# Sheet_Business_Card.net
KiCad netlist of a schematic drawn in Altium Designer
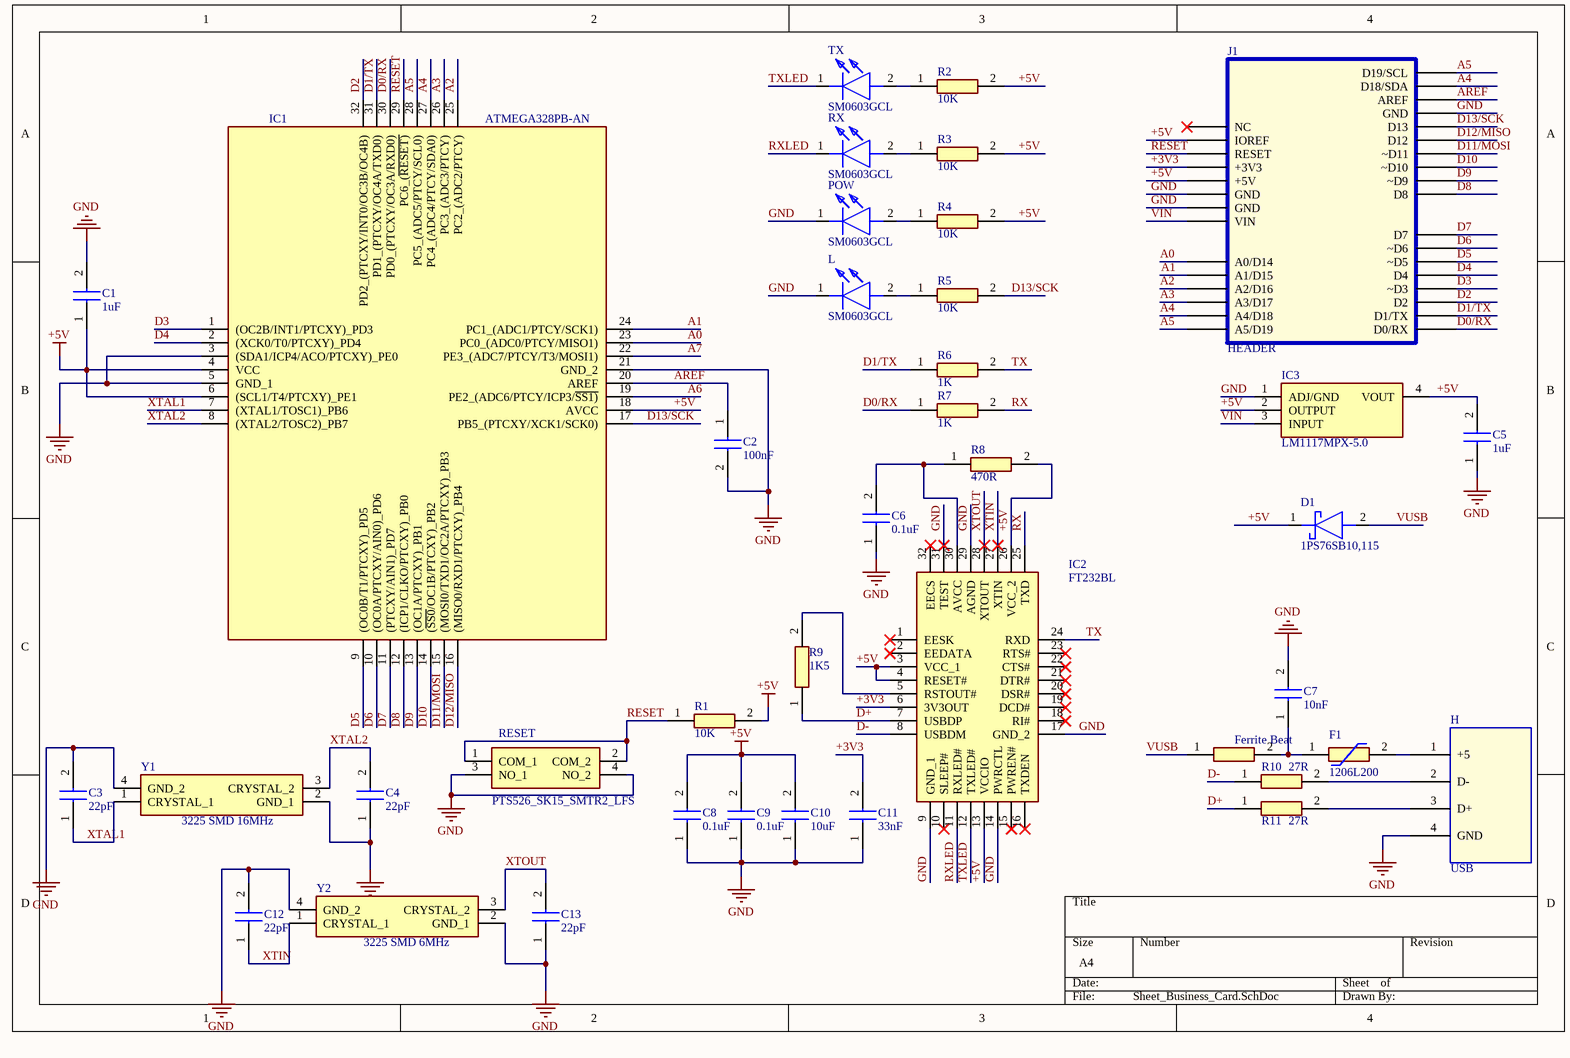
[diagram p0: Sheet_Business_Card.SchDoc]

(export (version "E")
  (design (tool "Eeschema 10.0.6"))
  (components
    (comp (ref "C1")
      (value "1uF")
      (footprint "SamacSys:CAPC1608X90N")
      (description "Capacitor")
      (fields
        (field (name "MANUFACTURER_PART_NUMBER") "06035C105KAT2A")
        (field (name "MOUSER PART NUMBER") "581-06035C105KAT2A")
      )
      (libsource (lib "*") (part "06035C105KAT2A"))
    )
    (comp (ref "C2")
      (value "100nF")
      (footprint "SamacSys:CAPC1608X90N")
      (description "Capacitor")
      (fields
        (field (name "MANUFACTURER_PART_NUMBER") "06035C105KAT2A")
        (field (name "MOUSER PART NUMBER") "581-06035C105KAT2A")
      )
      (libsource (lib "*") (part "06035C105KAT2A"))
    )
    (comp (ref "C3")
      (value "22pF")
      (footprint "SamacSys:CAPC1608X90N")
      (description "Capacitor")
      (fields
        (field (name "MANUFACTURER_PART_NUMBER") "06035C105KAT2A")
        (field (name "MOUSER PART NUMBER") "581-06035C105KAT2A")
      )
      (libsource (lib "*") (part "06035C105KAT2A"))
    )
    (comp (ref "C4")
      (value "22pF")
      (footprint "SamacSys:CAPC1608X90N")
      (description "Capacitor")
      (fields
        (field (name "MANUFACTURER_PART_NUMBER") "06035C105KAT2A")
        (field (name "MOUSER PART NUMBER") "581-06035C105KAT2A")
      )
      (libsource (lib "*") (part "06035C105KAT2A"))
    )
    (comp (ref "C5")
      (value "1uF")
      (footprint "SamacSys:CAPC1608X90N")
      (description "Capacitor")
      (fields
        (field (name "MANUFACTURER_PART_NUMBER") "06035C105KAT2A")
        (field (name "MOUSER PART NUMBER") "581-06035C105KAT2A")
      )
      (libsource (lib "*") (part "06035C105KAT2A"))
    )
    (comp (ref "C6")
      (value "0.1uF")
      (footprint "SamacSys:CAPC1608X90N")
      (description "Capacitor")
      (fields
        (field (name "MANUFACTURER_PART_NUMBER") "06035C105KAT2A")
        (field (name "MOUSER PART NUMBER") "581-06035C105KAT2A")
      )
      (libsource (lib "*") (part "06035C105KAT2A"))
    )
    (comp (ref "C7")
      (value "10nF")
      (footprint "SamacSys:CAPC1608X90N")
      (description "Capacitor")
      (fields
        (field (name "MANUFACTURER_PART_NUMBER") "06035C105KAT2A")
        (field (name "MOUSER PART NUMBER") "581-06035C105KAT2A")
      )
      (libsource (lib "*") (part "06035C105KAT2A"))
    )
    (comp (ref "C8")
      (value "0.1uF")
      (footprint "SamacSys:CAPC1608X90N")
      (description "Capacitor")
      (fields
        (field (name "MANUFACTURER_PART_NUMBER") "06035C105KAT2A")
        (field (name "MOUSER PART NUMBER") "581-06035C105KAT2A")
      )
      (libsource (lib "*") (part "06035C105KAT2A"))
    )
    (comp (ref "C9")
      (value "0.1uF")
      (footprint "SamacSys:CAPC1608X90N")
      (description "Capacitor")
      (fields
        (field (name "MANUFACTURER_PART_NUMBER") "06035C105KAT2A")
        (field (name "MOUSER PART NUMBER") "581-06035C105KAT2A")
      )
      (libsource (lib "*") (part "06035C105KAT2A"))
    )
    (comp (ref "C10")
      (value "10uF")
      (footprint "SamacSys:CAPC1608X90N")
      (description "Capacitor")
      (fields
        (field (name "MANUFACTURER_PART_NUMBER") "06035C105KAT2A")
        (field (name "MOUSER PART NUMBER") "581-06035C105KAT2A")
      )
      (libsource (lib "*") (part "06035C105KAT2A"))
    )
    (comp (ref "C11")
      (value "33nF")
      (footprint "SamacSys:CAPC1608X90N")
      (description "Capacitor")
      (fields
        (field (name "MANUFACTURER_PART_NUMBER") "06035C105KAT2A")
        (field (name "MOUSER PART NUMBER") "581-06035C105KAT2A")
      )
      (libsource (lib "*") (part "06035C105KAT2A"))
    )
    (comp (ref "C12")
      (value "22pF")
      (footprint "SamacSys:CAPC1608X90N")
      (description "Capacitor")
      (fields
        (field (name "MANUFACTURER_PART_NUMBER") "06035C105KAT2A")
        (field (name "MOUSER PART NUMBER") "581-06035C105KAT2A")
      )
      (libsource (lib "*") (part "06035C105KAT2A"))
    )
    (comp (ref "C13")
      (value "22pF")
      (footprint "SamacSys:CAPC1608X90N")
      (description "Capacitor")
      (fields
        (field (name "MANUFACTURER_PART_NUMBER") "06035C105KAT2A")
        (field (name "MOUSER PART NUMBER") "581-06035C105KAT2A")
      )
      (libsource (lib "*") (part "06035C105KAT2A"))
    )
    (comp (ref "D1")
      (value "1PS76SB10,115")
      (footprint "SamacSys:SOD2512X110N")
      (description "Schottky Diode")
      (fields (field (name "MOUSER PART NUMBER") "771-1PS76SB10-T/R"))
      (libsource (lib "SamacSys") (part "1PS76SB10,115"))
    )
    (comp (ref "F1")
      (value "1206L200")
      (footprint "SamacSys:1206L05015YR")
      (description "Resettable Fuse")
      (libsource (lib "SamacSys") (part "1206L200"))
    )
    (comp (ref "FB")
      (value "Ferrite Beat")
      (footprint "SamacSys:RESC1608X55N")
      (description "Resistor")
      (fields
        (field (name "MANUFACTURER_PART_NUMBER") "KTR03EZPF1501")
        (field (name "MOUSER PART NUMBER") "755-KTR03EZPF1501")
      )
      (libsource (lib "SamacSys") (part "KTR03EZPF1501"))
    )
    (comp (ref "H") (value "USB") (footprint "USB_FLAT") (libsource (lib "BisnessCard") (part "USB")))
    (comp (ref "IC1")
      (value "ATMEGA328PB-AN")
      (footprint "SamacSys:QFP80P900X900X120-32N")
      (description "Integrated Circuit")
      (fields (field (name "MOUSER PART NUMBER") "556-ATMEGA328PB-AN"))
      (libsource (lib "*") (part "ATMEGA328PB-AN"))
    )
    (comp (ref "IC2")
      (value "FT232BL")
      (footprint "SamacSys:QFP80P900X900X160-32N")
      (description "Integrated Circuit")
      (libsource (lib "*") (part "FT232BL"))
    )
    (comp (ref "IC3")
      (value "LM1117MPX-5.0")
      (footprint "SamacSys:SOT230P700X180-4N")
      (description "Integrated Circuit")
      (fields (field (name "MOUSER PART NUMBER") "926-LM1117MPX-50"))
      (libsource (lib "SamacSys") (part "LM1117MPX-5.0"))
    )
    (comp (ref "J1")
      (value "HEADER")
      (footprint "Conector Arduino UNO")
      (libsource (lib "BisnessCard") (part "HEDER ARDUINO UNO"))
    )
    (comp (ref "L")
      (value "SM0603GCL")
      (footprint "SamacSys:LEDC1608X60N")
      (description "LED")
      (fields (field (name "MOUSER PART NUMBER") "749-SM0603GCL"))
      (libsource (lib "SamacSys") (part "SM0603GCL"))
    )
    (comp (ref "POW")
      (value "SM0603GCL")
      (footprint "SamacSys:LEDC1608X60N")
      (description "LED")
      (fields (field (name "MOUSER PART NUMBER") "749-SM0603GCL"))
      (libsource (lib "SamacSys") (part "SM0603GCL"))
    )
    (comp (ref "R1")
      (value "10K")
      (footprint "SamacSys:RESC1608X55N")
      (description "Resistor")
      (fields
        (field (name "MANUFACTURER_PART_NUMBER") "KTR03EZPF1501")
        (field (name "MOUSER PART NUMBER") "755-KTR03EZPF1501")
      )
      (libsource (lib "SamacSys") (part "KTR03EZPF1501"))
    )
    (comp (ref "R2")
      (value "10K")
      (footprint "SamacSys:RESC1608X55N")
      (description "Resistor")
      (fields
        (field (name "MANUFACTURER_PART_NUMBER") "KTR03EZPF1501")
        (field (name "MOUSER PART NUMBER") "755-KTR03EZPF1501")
      )
      (libsource (lib "SamacSys") (part "KTR03EZPF1501"))
    )
    (comp (ref "R3")
      (value "10K")
      (footprint "SamacSys:RESC1608X55N")
      (description "Resistor")
      (fields
        (field (name "MANUFACTURER_PART_NUMBER") "KTR03EZPF1501")
        (field (name "MOUSER PART NUMBER") "755-KTR03EZPF1501")
      )
      (libsource (lib "SamacSys") (part "KTR03EZPF1501"))
    )
    (comp (ref "R4")
      (value "10K")
      (footprint "SamacSys:RESC1608X55N")
      (description "Resistor")
      (fields
        (field (name "MANUFACTURER_PART_NUMBER") "KTR03EZPF1501")
        (field (name "MOUSER PART NUMBER") "755-KTR03EZPF1501")
      )
      (libsource (lib "SamacSys") (part "KTR03EZPF1501"))
    )
    (comp (ref "R5")
      (value "10K")
      (footprint "SamacSys:RESC1608X55N")
      (description "Resistor")
      (fields
        (field (name "MANUFACTURER_PART_NUMBER") "KTR03EZPF1501")
        (field (name "MOUSER PART NUMBER") "755-KTR03EZPF1501")
      )
      (libsource (lib "SamacSys") (part "KTR03EZPF1501"))
    )
    (comp (ref "R6")
      (value "1K")
      (footprint "SamacSys:RESC1608X55N")
      (description "Resistor")
      (fields
        (field (name "MANUFACTURER_PART_NUMBER") "KTR03EZPF1501")
        (field (name "MOUSER PART NUMBER") "755-KTR03EZPF1501")
      )
      (libsource (lib "SamacSys") (part "KTR03EZPF1501"))
    )
    (comp (ref "R7")
      (value "1K")
      (footprint "SamacSys:RESC1608X55N")
      (description "Resistor")
      (fields
        (field (name "MANUFACTURER_PART_NUMBER") "KTR03EZPF1501")
        (field (name "MOUSER PART NUMBER") "755-KTR03EZPF1501")
      )
      (libsource (lib "SamacSys") (part "KTR03EZPF1501"))
    )
    (comp (ref "R8")
      (value "470R")
      (footprint "SamacSys:RESC1608X55N")
      (description "Resistor")
      (fields
        (field (name "MANUFACTURER_PART_NUMBER") "KTR03EZPF1501")
        (field (name "MOUSER PART NUMBER") "755-KTR03EZPF1501")
      )
      (libsource (lib "SamacSys") (part "KTR03EZPF1501"))
    )
    (comp (ref "R9")
      (value "1K5")
      (footprint "SamacSys:RESC1608X55N")
      (description "Resistor")
      (fields
        (field (name "MANUFACTURER_PART_NUMBER") "KTR03EZPF1501")
        (field (name "MOUSER PART NUMBER") "755-KTR03EZPF1501")
      )
      (libsource (lib "") (part "KTR03EZPF1501_1"))
    )
    (comp (ref "R10")
      (value "27R")
      (footprint "SamacSys:RESC1608X55N")
      (description "Resistor")
      (fields
        (field (name "MANUFACTURER_PART_NUMBER") "KTR03EZPF1501")
        (field (name "MOUSER PART NUMBER") "755-KTR03EZPF1501")
      )
      (libsource (lib "SamacSys") (part "KTR03EZPF1501"))
    )
    (comp (ref "R11")
      (value "27R")
      (footprint "SamacSys:RESC1608X55N")
      (description "Resistor")
      (fields
        (field (name "MANUFACTURER_PART_NUMBER") "KTR03EZPF1501")
        (field (name "MOUSER PART NUMBER") "755-KTR03EZPF1501")
      )
      (libsource (lib "SamacSys") (part "KTR03EZPF1501"))
    )
    (comp (ref "RESET")
      (value "PTS526_SK15_SMTR2_LFS")
      (footprint "SamacSys:PTS526SK15SMTR2LFS")
      (description "Switch")
      (fields
        (field (name "MANUFACTURER_PART_NUMBER") "PTS526 SK15 SMTR2 LFS")
        (field (name "MOUSER PART NUMBER") "611-PTS526SK15SMR2L")
      )
      (libsource (lib "*") (part "PTS526_SK15_SMTR2_LFS"))
    )
    (comp (ref "RX")
      (value "SM0603GCL")
      (footprint "SamacSys:LEDC1608X60N")
      (description "LED")
      (fields (field (name "MOUSER PART NUMBER") "749-SM0603GCL"))
      (libsource (lib "SamacSys") (part "SM0603GCL"))
    )
    (comp (ref "TX")
      (value "SM0603GCL")
      (footprint "SamacSys:LEDC1608X60N")
      (description "LED")
      (fields (field (name "MOUSER PART NUMBER") "749-SM0603GCL"))
      (libsource (lib "SamacSys") (part "SM0603GCL"))
    )
    (comp (ref "Y1")
      (value "TSX-3225_16.0000MF18X-AC0")
      (footprint "SamacSys:TSX3225160000MF18XAC0")
      (description "Crystal or Oscillator 16MHz")
      (fields
        (field (name "MANUFACTURER_PART_NUMBER") "TSX-3225 16.0000MF18X-AC0")
        (field (name "MOUSER PART NUMBER") "732-322516F18XAC0")
      )
      (libsource (lib "*") (part "TSX-3225_16.0000MF18X-AC0"))
    )
    (comp (ref "Y2")
      (value "TSX-3225_16.0000MF18X-AC0")
      (footprint "SamacSys:TSX3225160000MF18XAC0")
      (description "Crystal or Oscillator 6 MHz")
      (fields
        (field (name "MANUFACTURER_PART_NUMBER") "TSX-3225 16.0000MF18X-AC0")
        (field (name "MOUSER PART NUMBER") "732-322516F18XAC0")
      )
      (libsource (lib "*") (part "TSX-3225_16.0000MF18X-AC0"))
    )
  )
  (nets
    (net (code "1") (name "+5V") (class "Default")
      (node (ref "C1") (pin "1") (pinfunction "1_1") (pintype "passive"))
      (node (ref "C10") (pin "2") (pinfunction "2_2") (pintype "passive"))
      (node (ref "C5") (pin "2") (pinfunction "2_2") (pintype "passive"))
      (node (ref "C8") (pin "2") (pinfunction "2_2") (pintype "passive"))
      (node (ref "C9") (pin "2") (pinfunction "2_2") (pintype "passive"))
      (node (ref "D1") (pin "1") (pinfunction "K_1") (pintype "passive"))
      (node (ref "IC1") (pin "18") (pinfunction "AVCC_18") (pintype "passive"))
      (node (ref "IC1") (pin "4") (pinfunction "VCC_4") (pintype "passive"))
      (node (ref "IC1") (pin "6") (pinfunction "(SCL1/T4/PTCXY)_PE1_6") (pintype "passive"))
      (node (ref "IC2") (pin "13") (pinfunction "VCCIO_13") (pintype "passive"))
      (node (ref "IC2") (pin "26") (pinfunction "VCC_2_26") (pintype "passive"))
      (node (ref "IC2") (pin "3") (pinfunction "VCC_1_3") (pintype "passive"))
      (node (ref "IC2") (pin "4") (pinfunction "RESET#_4") (pintype "passive"))
      (node (ref "IC3") (pin "2") (pinfunction "OUTPUT_2") (pintype "passive"))
      (node (ref "IC3") (pin "4") (pinfunction "VOUT_4") (pintype "passive"))
      (node (ref "J1") (pin "4") (pinfunction "IOREF_4") (pintype "passive"))
      (node (ref "R1") (pin "2") (pinfunction "2_2") (pintype "passive"))
      (node (ref "R2") (pin "2") (pinfunction "2_2") (pintype "passive"))
      (node (ref "R3") (pin "2") (pinfunction "2_2") (pintype "passive"))
      (node (ref "R4") (pin "2") (pinfunction "2_2") (pintype "passive"))
      (node (ref "R8") (pin "2") (pinfunction "2_2") (pintype "passive"))
    )
    (net (code "2") (name "/+3V3") (class "Default")
      (node (ref "C11") (pin "2") (pinfunction "2_2") (pintype "passive"))
      (node (ref "IC2") (pin "6") (pinfunction "3V3OUT_6") (pintype "passive"))
      (node (ref "J1") (pin "6") (pinfunction "+3V3_6") (pintype "passive"))
    )
    (net (code "3") (name "/A0") (class "Default")
      (node (ref "IC1") (pin "23") (pinfunction "PC0_(ADC0/PTCY/MISO1)_23") (pintype "passive"))
      (node (ref "J1") (pin "23") (pinfunction "A0/D14_23") (pintype "passive"))
    )
    (net (code "4") (name "/A1") (class "Default")
      (node (ref "IC1") (pin "24") (pinfunction "PC1_(ADC1/PTCY/SCK1)_24") (pintype "passive"))
      (node (ref "J1") (pin "24") (pinfunction "A1/D15_24") (pintype "passive"))
    )
    (net (code "5") (name "/A2") (class "Default")
      (node (ref "IC1") (pin "25") (pinfunction "PC2_(ADC2/PTCY)_25") (pintype "passive"))
      (node (ref "J1") (pin "25") (pinfunction "A2/D16_25") (pintype "passive"))
    )
    (net (code "6") (name "/A3") (class "Default")
      (node (ref "IC1") (pin "26") (pinfunction "PC3_(ADC3/PTCY)_26") (pintype "passive"))
      (node (ref "J1") (pin "26") (pinfunction "A3/D17_26") (pintype "passive"))
    )
    (net (code "7") (name "/A4") (class "Default")
      (node (ref "IC1") (pin "27") (pinfunction "PC4_(ADC4/PTCY/SDA0)_27") (pintype "passive"))
      (node (ref "J1") (pin "27") (pinfunction "A4/D18_27") (pintype "passive"))
    )
    (net (code "8") (name "/A5") (class "Default")
      (node (ref "IC1") (pin "28") (pinfunction "PC5_(ADC5/PTCY/SCL0)_28") (pintype "passive"))
      (node (ref "J1") (pin "28") (pinfunction "A5/D19_28") (pintype "passive"))
    )
    (net (code "9") (name "/A6") (class "Default")
      (node (ref "IC1") (pin "19") (pinfunction "PE2_(ADC6/PTCY/ICP3/~{SS1)}_19") (pintype "passive"))
    )
    (net (code "10") (name "/A7") (class "Default")
      (node (ref "IC1") (pin "22") (pinfunction "PE3_(ADC7/PTCY/T3/MOSI1)_22") (pintype "passive"))
    )
    (net (code "11") (name "/AREF") (class "Default")
      (node (ref "C2") (pin "1") (pinfunction "1_1") (pintype "passive"))
      (node (ref "IC1") (pin "20") (pinfunction "AREF_20") (pintype "passive"))
      (node (ref "J1") (pin "20") (pinfunction "AREF_20") (pintype "passive"))
    )
    (net (code "12") (name "/D+") (class "Default")
      (node (ref "IC2") (pin "7") (pinfunction "USBDP_7") (pintype "passive"))
      (node (ref "R11") (pin "1") (pinfunction "1_1") (pintype "passive"))
      (node (ref "R9") (pin "1") (pinfunction "1_1") (pintype "passive"))
    )
    (net (code "13") (name "/D-") (class "Default")
      (node (ref "IC2") (pin "8") (pinfunction "USBDM_8") (pintype "passive"))
      (node (ref "R10") (pin "1") (pinfunction "1_1") (pintype "passive"))
    )
    (net (code "14") (name "/D0{slash}RX") (class "Default")
      (node (ref "IC1") (pin "30") (pinfunction "PD0_(PTCXY/OC3A/RXD0)_30") (pintype "passive"))
      (node (ref "J1") (pin "30") (pinfunction "D0/RX_30") (pintype "passive"))
      (node (ref "R7") (pin "1") (pinfunction "1_1") (pintype "passive"))
    )
    (net (code "15") (name "/D1{slash}TX") (class "Default")
      (node (ref "IC1") (pin "31") (pinfunction "PD1_(PTCXY/OC4A/TXD0)_31") (pintype "passive"))
      (node (ref "J1") (pin "31") (pinfunction "D1/TX_31") (pintype "passive"))
      (node (ref "R6") (pin "1") (pinfunction "1_1") (pintype "passive"))
    )
    (net (code "16") (name "/D2") (class "Default")
      (node (ref "IC1") (pin "32") (pinfunction "PD2_(PTCXY/INT0/OC3B/OC4B)_32") (pintype "passive"))
      (node (ref "J1") (pin "32") (pinfunction "D2_32") (pintype "passive"))
    )
    (net (code "17") (name "/D3") (class "Default")
      (node (ref "IC1") (pin "1") (pinfunction "(OC2B/INT1/PTCXY)_PD3_1") (pintype "passive"))
      (node (ref "J1") (pin "1") (pinfunction "~D3_1") (pintype "passive"))
    )
    (net (code "18") (name "/D4") (class "Default")
      (node (ref "IC1") (pin "2") (pinfunction "(XCK0/T0/PTCXY)_PD4_2") (pintype "passive"))
      (node (ref "J1") (pin "2") (pinfunction "D4_2") (pintype "passive"))
    )
    (net (code "19") (name "/D5") (class "Default")
      (node (ref "IC1") (pin "9") (pinfunction "(OC0B/T1/PTCXY)_PD5_9") (pintype "passive"))
      (node (ref "J1") (pin "9") (pinfunction "~D5_9") (pintype "passive"))
    )
    (net (code "20") (name "/D6") (class "Default")
      (node (ref "IC1") (pin "10") (pinfunction "(OC0A/PTCXY/AIN0)_PD6_10") (pintype "passive"))
      (node (ref "J1") (pin "10") (pinfunction "~D6_10") (pintype "passive"))
    )
    (net (code "21") (name "/D7") (class "Default")
      (node (ref "IC1") (pin "11") (pinfunction "(PTCXY/AIN1)_PD7_11") (pintype "passive"))
      (node (ref "J1") (pin "11") (pinfunction "D7_11") (pintype "passive"))
    )
    (net (code "22") (name "/D8") (class "Default")
      (node (ref "IC1") (pin "12") (pinfunction "(ICP1/CLKO/PTCXY)_PB0_12") (pintype "passive"))
      (node (ref "J1") (pin "12") (pinfunction "D8_12") (pintype "passive"))
    )
    (net (code "23") (name "/D9") (class "Default")
      (node (ref "IC1") (pin "13") (pinfunction "(OC1A/PTCXY)_PB1_13") (pintype "passive"))
      (node (ref "J1") (pin "13") (pinfunction "~D9_13") (pintype "passive"))
    )
    (net (code "24") (name "/D10") (class "Default")
      (node (ref "IC1") (pin "14") (pinfunction "(~{SS0}/OC1B/PTCXY)_PB2_14") (pintype "passive"))
      (node (ref "J1") (pin "14") (pinfunction "~D10_14") (pintype "passive"))
    )
    (net (code "25") (name "/D11{slash}MOSI") (class "Default")
      (node (ref "IC1") (pin "15") (pinfunction "(MOSI0/TXD1/OC2A/PTCXY)_PB3_15") (pintype "passive"))
      (node (ref "J1") (pin "15") (pinfunction "~D11_15") (pintype "passive"))
    )
    (net (code "26") (name "/D12{slash}MISO") (class "Default")
      (node (ref "IC1") (pin "16") (pinfunction "(MISO0/RXD1/PTCXY)_PB4_16") (pintype "passive"))
      (node (ref "J1") (pin "16") (pinfunction "D12_16") (pintype "passive"))
    )
    (net (code "27") (name "/D13{slash}SCK") (class "Default")
      (node (ref "IC1") (pin "17") (pinfunction "PB5_(PTCXY/XCK1/SCK0)_17") (pintype "passive"))
      (node (ref "J1") (pin "17") (pinfunction "D13_17") (pintype "passive"))
      (node (ref "R5") (pin "2") (pinfunction "2_2") (pintype "passive"))
    )
    (net (code "28") (name "/RESET") (class "Default")
      (node (ref "IC1") (pin "29") (pinfunction "PC6_(~{RESET)}_29") (pintype "passive"))
      (node (ref "J1") (pin "29") (pinfunction "RESET_29") (pintype "passive"))
      (node (ref "R1") (pin "1") (pinfunction "1_1") (pintype "passive"))
      (node (ref "RESET") (pin "1") (pinfunction "COM_1_1") (pintype "passive"))
      (node (ref "RESET") (pin "2") (pinfunction "COM_2_2") (pintype "passive"))
    )
    (net (code "29") (name "/RX") (class "Default")
      (node (ref "IC2") (pin "25") (pinfunction "TXD_25") (pintype "passive"))
      (node (ref "R7") (pin "2") (pinfunction "2_2") (pintype "passive"))
    )
    (net (code "30") (name "/RXLED") (class "Default")
      (node (ref "IC2") (pin "11") (pinfunction "RXLED#_11") (pintype "passive"))
      (node (ref "RX") (pin "1") (pinfunction "K_1") (pintype "passive"))
    )
    (net (code "31") (name "/TX") (class "Default")
      (node (ref "IC2") (pin "24") (pinfunction "RXD_24") (pintype "passive"))
      (node (ref "R6") (pin "2") (pinfunction "2_2") (pintype "passive"))
    )
    (net (code "32") (name "/TXLED") (class "Default")
      (node (ref "IC2") (pin "12") (pinfunction "TXLED#_12") (pintype "passive"))
      (node (ref "TX") (pin "1") (pinfunction "K_1") (pintype "passive"))
    )
    (net (code "33") (name "/VIN") (class "Default")
      (node (ref "IC3") (pin "3") (pinfunction "INPUT_3") (pintype "passive"))
      (node (ref "J1") (pin "33") (pinfunction "VIN_33") (pintype "passive"))
    )
    (net (code "34") (name "/VUSB") (class "Default")
      (node (ref "D1") (pin "2") (pinfunction "A_2") (pintype "passive"))
      (node (ref "FB") (pin "1") (pinfunction "1_1") (pintype "passive"))
    )
    (net (code "35") (name "/XTAL1") (class "Default")
      (node (ref "C3") (pin "1") (pinfunction "1_1") (pintype "passive"))
      (node (ref "IC1") (pin "7") (pinfunction "(XTAL1/TOSC1)_PB6_7") (pintype "passive"))
      (node (ref "Y1") (pin "1") (pinfunction "CRYSTAL_1_1") (pintype "passive"))
    )
    (net (code "36") (name "/XTAL2") (class "Default")
      (node (ref "C4") (pin "2") (pinfunction "2_2") (pintype "passive"))
      (node (ref "IC1") (pin "8") (pinfunction "(XTAL2/TOSC2)_PB7_8") (pintype "passive"))
      (node (ref "Y1") (pin "3") (pinfunction "CRYSTAL_2_3") (pintype "passive"))
    )
    (net (code "37") (name "/XTIN") (class "Default")
      (node (ref "C12") (pin "1") (pinfunction "1_1") (pintype "passive"))
      (node (ref "IC2") (pin "27") (pinfunction "XTIN_27") (pintype "passive"))
      (node (ref "Y2") (pin "1") (pinfunction "CRYSTAL_1_1") (pintype "passive"))
    )
    (net (code "38") (name "/XTOUT") (class "Default")
      (node (ref "C13") (pin "2") (pinfunction "2_2") (pintype "passive"))
      (node (ref "IC2") (pin "28") (pinfunction "XTOUT_28") (pintype "passive"))
      (node (ref "Y2") (pin "3") (pinfunction "CRYSTAL_2_3") (pintype "passive"))
    )
    (net (code "39") (name "GND") (class "Default")
      (node (ref "C1") (pin "2") (pinfunction "2_2") (pintype "passive"))
      (node (ref "C10") (pin "1") (pinfunction "1_1") (pintype "passive"))
      (node (ref "C11") (pin "1") (pinfunction "1_1") (pintype "passive"))
      (node (ref "C12") (pin "2") (pinfunction "2_2") (pintype "passive"))
      (node (ref "C13") (pin "1") (pinfunction "1_1") (pintype "passive"))
      (node (ref "C2") (pin "2") (pinfunction "2_2") (pintype "passive"))
      (node (ref "C3") (pin "2") (pinfunction "2_2") (pintype "passive"))
      (node (ref "C4") (pin "1") (pinfunction "1_1") (pintype "passive"))
      (node (ref "C5") (pin "1") (pinfunction "1_1") (pintype "passive"))
      (node (ref "C6") (pin "1") (pinfunction "1_1") (pintype "passive"))
      (node (ref "C7") (pin "2") (pinfunction "2_2") (pintype "passive"))
      (node (ref "C8") (pin "1") (pinfunction "1_1") (pintype "passive"))
      (node (ref "C9") (pin "1") (pinfunction "1_1") (pintype "passive"))
      (node (ref "H") (pin "4") (pinfunction "GND_4") (pintype "passive"))
      (node (ref "IC1") (pin "21") (pinfunction "GND_2_21") (pintype "passive"))
      (node (ref "IC1") (pin "3") (pinfunction "(SDA1/ICP4/ACO/PTCXY)_PE0_3") (pintype "passive"))
      (node (ref "IC1") (pin "5") (pinfunction "GND_1_5") (pintype "passive"))
      (node (ref "IC2") (pin "14") (pinfunction "PWRCTL_14") (pintype "passive"))
      (node (ref "IC2") (pin "17") (pinfunction "GND_2_17") (pintype "passive"))
      (node (ref "IC2") (pin "29") (pinfunction "AGND_29") (pintype "passive"))
      (node (ref "IC2") (pin "31") (pinfunction "TEST_31") (pintype "passive"))
      (node (ref "IC2") (pin "9") (pinfunction "GND_1_9") (pintype "passive"))
      (node (ref "IC3") (pin "1") (pinfunction "ADJ/GND_1") (pintype "passive"))
      (node (ref "J1") (pin "21") (pinfunction "GND_21") (pintype "passive"))
      (node (ref "J1") (pin "3") (pinfunction "GND_3") (pintype "passive"))
      (node (ref "J1") (pin "5") (pinfunction "GND_5") (pintype "passive"))
      (node (ref "L") (pin "1") (pinfunction "K_1") (pintype "passive"))
      (node (ref "POW") (pin "1") (pinfunction "K_1") (pintype "passive"))
      (node (ref "RESET") (pin "3") (pinfunction "NO_1_3") (pintype "passive"))
      (node (ref "RESET") (pin "4") (pinfunction "NO_2_4") (pintype "passive"))
      (node (ref "Y1") (pin "2") (pinfunction "GND_1_2") (pintype "passive"))
      (node (ref "Y1") (pin "4") (pinfunction "GND_2_4") (pintype "passive"))
      (node (ref "Y2") (pin "2") (pinfunction "GND_1_2") (pintype "passive"))
      (node (ref "Y2") (pin "4") (pinfunction "GND_2_4") (pintype "passive"))
    )
    (net (code "40") (name "Net-(C7-Pad1)") (class "Default")
      (node (ref "C7") (pin "1") (pinfunction "1_1") (pintype "passive"))
      (node (ref "F1") (pin "1") (pinfunction "1_1") (pintype "passive"))
      (node (ref "FB") (pin "2") (pinfunction "2_2") (pintype "passive"))
    )
    (net (code "41") (name "Net-(H-+5)") (class "Default")
      (node (ref "F1") (pin "2") (pinfunction "2_2") (pintype "passive"))
      (node (ref "H") (pin "1") (pinfunction "+5_1") (pintype "passive"))
    )
    (net (code "42") (name "Net-(H-D+)") (class "Default")
      (node (ref "H") (pin "3") (pinfunction "D+_3") (pintype "passive"))
      (node (ref "R11") (pin "2") (pinfunction "2_2") (pintype "passive"))
    )
    (net (code "43") (name "Net-(H-D-)") (class "Default")
      (node (ref "H") (pin "2") (pinfunction "D-_2") (pintype "passive"))
      (node (ref "R10") (pin "2") (pinfunction "2_2") (pintype "passive"))
    )
    (net (code "44") (name "Net-(IC2-AVCC)") (class "Default")
      (node (ref "C6") (pin "2") (pinfunction "2_2") (pintype "passive"))
      (node (ref "IC2") (pin "30") (pinfunction "AVCC_30") (pintype "passive"))
      (node (ref "R8") (pin "1") (pinfunction "1_1") (pintype "passive"))
    )
    (net (code "45") (name "Net-(IC2-RSTOUT#)") (class "Default")
      (node (ref "IC2") (pin "5") (pinfunction "RSTOUT#_5") (pintype "passive"))
      (node (ref "R9") (pin "2") (pinfunction "2_2") (pintype "passive"))
    )
    (net (code "46") (name "Net-(L-A)") (class "Default")
      (node (ref "L") (pin "2") (pinfunction "A_2") (pintype "passive"))
      (node (ref "R5") (pin "1") (pinfunction "1_1") (pintype "passive"))
    )
    (net (code "47") (name "Net-(POW-A)") (class "Default")
      (node (ref "POW") (pin "2") (pinfunction "A_2") (pintype "passive"))
      (node (ref "R4") (pin "1") (pinfunction "1_1") (pintype "passive"))
    )
    (net (code "48") (name "Net-(RX-A)") (class "Default")
      (node (ref "R3") (pin "1") (pinfunction "1_1") (pintype "passive"))
      (node (ref "RX") (pin "2") (pinfunction "A_2") (pintype "passive"))
    )
    (net (code "49") (name "Net-(TX-A)") (class "Default")
      (node (ref "R2") (pin "1") (pinfunction "1_1") (pintype "passive"))
      (node (ref "TX") (pin "2") (pinfunction "A_2") (pintype "passive"))
    )
    (net (code "50") (name "unconnected-(IC2-CTS#-Pad22)") (class "Default")
      (node (ref "IC2") (pin "22") (pinfunction "CTS#_22") (pintype "passive+no_connect"))
    )
    (net (code "51") (name "unconnected-(IC2-DCD#-Pad19)") (class "Default")
      (node (ref "IC2") (pin "19") (pinfunction "DCD#_19") (pintype "passive+no_connect"))
    )
    (net (code "52") (name "unconnected-(IC2-DSR#-Pad20)") (class "Default")
      (node (ref "IC2") (pin "20") (pinfunction "DSR#_20") (pintype "passive+no_connect"))
    )
    (net (code "53") (name "unconnected-(IC2-DTR#-Pad21)") (class "Default")
      (node (ref "IC2") (pin "21") (pinfunction "DTR#_21") (pintype "passive+no_connect"))
    )
    (net (code "54") (name "unconnected-(IC2-EECS-Pad32)") (class "Default")
      (node (ref "IC2") (pin "32") (pinfunction "EECS_32") (pintype "passive+no_connect"))
    )
    (net (code "55") (name "unconnected-(IC2-EEDATA-Pad2)") (class "Default")
      (node (ref "IC2") (pin "2") (pinfunction "EEDATA_2") (pintype "passive+no_connect"))
    )
    (net (code "56") (name "unconnected-(IC2-EESK-Pad1)") (class "Default")
      (node (ref "IC2") (pin "1") (pinfunction "EESK_1") (pintype "passive+no_connect"))
    )
    (net (code "57") (name "unconnected-(IC2-PWREN#-Pad15)") (class "Default")
      (node (ref "IC2") (pin "15") (pinfunction "PWREN#_15") (pintype "passive+no_connect"))
    )
    (net (code "58") (name "unconnected-(IC2-RI#-Pad18)") (class "Default")
      (node (ref "IC2") (pin "18") (pinfunction "RI#_18") (pintype "passive+no_connect"))
    )
    (net (code "59") (name "unconnected-(IC2-RTS#-Pad23)") (class "Default")
      (node (ref "IC2") (pin "23") (pinfunction "RTS#_23") (pintype "passive+no_connect"))
    )
    (net (code "60") (name "unconnected-(IC2-SLEEP#-Pad10)") (class "Default")
      (node (ref "IC2") (pin "10") (pinfunction "SLEEP#_10") (pintype "passive+no_connect"))
    )
    (net (code "61") (name "unconnected-(IC2-TXDEN-Pad16)") (class "Default")
      (node (ref "IC2") (pin "16") (pinfunction "TXDEN_16") (pintype "passive+no_connect"))
    )
    (net (code "62") (name "unconnected-(J1-NC-Pad)") (class "Default")
      (node (ref "J1") (pin "") (pinfunction "NC_") (pintype "passive+no_connect"))
    )
  )
)
